# 4c_-_Latching_BSPD.net
KiCad netlist of a schematic drawn in Altium Designer
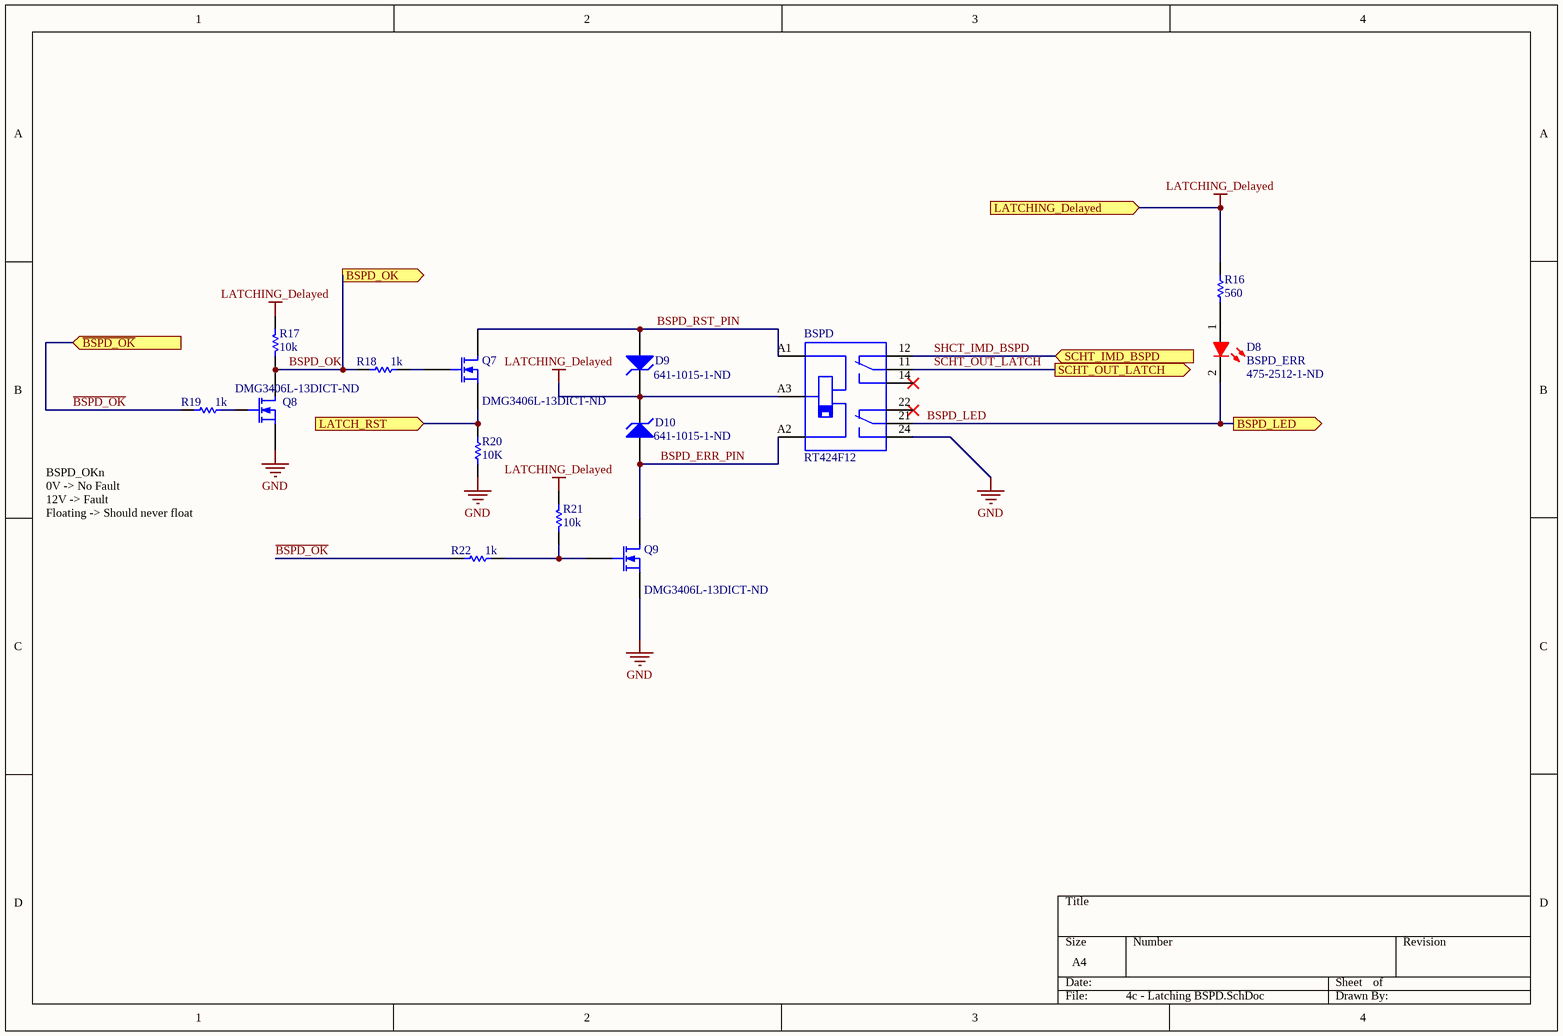
[diagram p0: 4c - Latching BSPD.SchDoc]

(export (version "E")
  (design (tool "Eeschema 10.0.6"))
  (components
    (comp (ref "BSPD")
      (value "RT424F12")
      (footprint "TE_5-1393243-4")
      (description "General Purpose Relay DPDT (2 Form C) 12VDC Coil Through Hole")
      (fields (field (name "MF") "TE Connectivity"))
      (libsource (lib "RT424F12") (part "RT424F12"))
    )
    (comp (ref "D8")
      (value "BSPD_ERR")
      (footprint "TOSH-0603LED_RED_V")
      (description "LED, Red 0603 (1608) 63mCd")
      (fields
        (field (name "MANUFACTURER") "Toshiba")
        (field (name "PARTNUMBER") "TLSU1008A(T04)")
        (field (name "SUPPLIER PART NUMBER 1") "475-2512-1-ND")
      )
      (libsource (lib "Altium Content Vault") (part "CMP-0444-00001-1"))
    )
    (comp (ref "D9")
      (value "D Zener")
      (footprint "DO214AC")
      (description "Zener Diode")
      (fields
        (field (name "SUPPLIER PART NUMBER 1") "641-1015-1-ND")
        (field (name "PUBLISHER") "Altium Limited")
      )
      (libsource (lib "Miscellaneous Devices") (part "D Zener"))
    )
    (comp (ref "D10")
      (value "D Zener")
      (footprint "DO214AC")
      (description "Zener Diode")
      (fields
        (field (name "SUPPLIER PART NUMBER 1") "641-1015-1-ND")
        (field (name "PUBLISHER") "Altium Limited")
      )
      (libsource (lib "Miscellaneous Devices") (part "D Zener"))
    )
    (comp (ref "Q7")
      (value "~")
      (footprint "SOT-23_N")
      (description "N-Channel MOSFET")
      (fields
        (field (name "MANUFACTURER") "Infineon Technologies")
        (field (name "SUPPLIER PART NUMBER 1") "DMG3406L-13DICT-ND")
        (field (name "PUBLISHER") "Altium Limited")
      )
      (libsource (lib "Miscellaneous Devices") (part "MOSFET-N"))
    )
    (comp (ref "Q8")
      (value "~")
      (footprint "SOT-23_N")
      (description "N-Channel MOSFET")
      (fields
        (field (name "MANUFACTURER") "Infineon Technologies")
        (field (name "SUPPLIER PART NUMBER 1") "DMG3406L-13DICT-ND")
        (field (name "PUBLISHER") "Altium Limited")
      )
      (libsource (lib "Miscellaneous Devices") (part "MOSFET-N"))
    )
    (comp (ref "Q9")
      (value "~")
      (footprint "SOT-23_N")
      (description "N-Channel MOSFET")
      (fields
        (field (name "MANUFACTURER") "Infineon Technologies")
        (field (name "SUPPLIER PART NUMBER 1") "DMG3406L-13DICT-ND")
        (field (name "PUBLISHER") "Altium Limited")
      )
      (libsource (lib "Miscellaneous Devices") (part "MOSFET-N"))
    )
    (comp (ref "R16")
      (value "560")
      (footprint "RESC0603(1608)_L")
      (description "0603 (1608 Metric) Chip Resistor")
      (libsource (lib "Altium Content Vault") (part "RES_3"))
    )
    (comp (ref "R17")
      (value "RHM1.0KDCT-ND")
      (footprint "1608[0603]")
      (description "RES SMD 1.0K OHM 5% 1/4W 0603")
      (fields
        (field (name "MANUFACTURER") "Rohm Semiconductor")
        (field (name "MANUFACTURER PART NUMBER") "ESR03EZPJ102")
        (field (name "RESISTANCE (OHMS)") "10k")
      )
      (libsource (lib "Miscellaneous Devices") (part "Res1"))
    )
    (comp (ref "R18")
      (value "1k")
      (footprint "1608[0603]")
      (description "RES SMD 100 OHM 5% 1/4W 0603")
      (fields
        (field (name "MANUFACTURER") "Rohm Semiconductor")
        (field (name "MANUFACTURER PART NUMBER") "ESR03EZPJ101")
        (field (name "PUBLISHER") "Altium Limited")
      )
      (libsource (lib "Miscellaneous Devices") (part "Res1"))
    )
    (comp (ref "R19")
      (value "1k")
      (footprint "1608[0603]")
      (description "RES SMD 100 OHM 5% 1/4W 0603")
      (fields
        (field (name "MANUFACTURER") "Rohm Semiconductor")
        (field (name "MANUFACTURER PART NUMBER") "ESR03EZPJ101")
        (field (name "PUBLISHER") "Altium Limited")
      )
      (libsource (lib "Miscellaneous Devices") (part "Res1"))
    )
    (comp (ref "R20")
      (value "10K")
      (footprint "1608[0603]")
      (description "RES SMD 10K OHM 5% 1/4W 0603")
      (fields
        (field (name "MANUFACTURER") "Rohm Semiconductor")
        (field (name "MANUFACTURER PART NUMBER") "ESR03EZPJ103")
        (field (name "PUBLISHER") "Altium Limited")
      )
      (libsource (lib "Miscellaneous Devices") (part "Res1"))
    )
    (comp (ref "R21")
      (value "RHM1.0KDCT-ND")
      (footprint "1608[0603]")
      (description "RES SMD 1.0K OHM 5% 1/4W 0603")
      (fields
        (field (name "MANUFACTURER") "Rohm Semiconductor")
        (field (name "MANUFACTURER PART NUMBER") "ESR03EZPJ102")
        (field (name "RESISTANCE (OHMS)") "10k")
      )
      (libsource (lib "Miscellaneous Devices") (part "Res1"))
    )
    (comp (ref "R22")
      (value "1k")
      (footprint "1608[0603]")
      (description "RES SMD 100 OHM 5% 1/4W 0603")
      (fields
        (field (name "MANUFACTURER") "Rohm Semiconductor")
        (field (name "MANUFACTURER PART NUMBER") "ESR03EZPJ101")
        (field (name "PUBLISHER") "Altium Limited")
      )
      (libsource (lib "Miscellaneous Devices") (part "Res1"))
    )
  )
  (nets
    (net (code "1") (name "/BSPD_ERR_PIN") (class "Default")
      (node (ref "BSPD") (pin "A2") (pinfunction "A2_A2") (pintype "passive"))
      (node (ref "D10") (pin "1") (pinfunction "A_1") (pintype "passive"))
      (node (ref "Q9") (pin "3") (pinfunction "D_3") (pintype "passive"))
    )
    (net (code "2") (name "/BSPD_LED") (class "Default")
      (node (ref "BSPD") (pin "21") (pinfunction "21_21") (pintype "passive"))
      (node (ref "D8") (pin "2") (pinfunction "K_2") (pintype "passive"))
    )
    (net (code "3") (name "/BSPD_OK") (class "Default")
      (node (ref "Q8") (pin "3") (pinfunction "D_3") (pintype "passive"))
      (node (ref "R17") (pin "2") (pinfunction "2_2") (pintype "passive"))
      (node (ref "R18") (pin "1") (pinfunction "1_1") (pintype "passive"))
    )
    (net (code "4") (name "/BSPD_RST_PIN") (class "Default")
      (node (ref "BSPD") (pin "A1") (pinfunction "A1_A1") (pintype "passive"))
      (node (ref "D9") (pin "1") (pinfunction "A_1") (pintype "passive"))
      (node (ref "Q7") (pin "3") (pinfunction "D_3") (pintype "passive"))
    )
    (net (code "5") (name "/LATCH_RST") (class "Default")
      (node (ref "Q7") (pin "2") (pinfunction "S_2") (pintype "passive"))
      (node (ref "R20") (pin "2") (pinfunction "2_2") (pintype "passive"))
    )
    (net (code "6") (name "/SCHT_OUT_LATCH") (class "Default")
      (node (ref "BSPD") (pin "11") (pinfunction "11_11") (pintype "passive"))
    )
    (net (code "7") (name "/SHCT_IMD_BSPD") (class "Default")
      (node (ref "BSPD") (pin "12") (pinfunction "12_12") (pintype "passive"))
    )
    (net (code "8") (name "/~{BSPD_OK}") (class "Default")
      (node (ref "R19") (pin "1") (pinfunction "1_1") (pintype "passive"))
      (node (ref "R22") (pin "1") (pinfunction "1_1") (pintype "passive"))
    )
    (net (code "9") (name "GND") (class "Default")
      (node (ref "BSPD") (pin "24") (pinfunction "24_24") (pintype "passive"))
      (node (ref "Q8") (pin "2") (pinfunction "S_2") (pintype "passive"))
      (node (ref "Q9") (pin "2") (pinfunction "S_2") (pintype "passive"))
      (node (ref "R20") (pin "1") (pinfunction "1_1") (pintype "passive"))
    )
    (net (code "10") (name "LATCHING_Delayed") (class "Default")
      (node (ref "BSPD") (pin "A3") (pinfunction "A3_A3") (pintype "passive"))
      (node (ref "D10") (pin "2") (pinfunction "K_2") (pintype "passive"))
      (node (ref "D9") (pin "2") (pinfunction "K_2") (pintype "passive"))
      (node (ref "R16") (pin "2") (pinfunction "2_2") (pintype "passive"))
      (node (ref "R17") (pin "1") (pinfunction "1_1") (pintype "passive"))
      (node (ref "R21") (pin "1") (pinfunction "1_1") (pintype "passive"))
    )
    (net (code "11") (name "Net-(D8-A)") (class "Default")
      (node (ref "D8") (pin "1") (pinfunction "A_1") (pintype "passive"))
      (node (ref "R16") (pin "1") (pinfunction "1_1") (pintype "passive"))
    )
    (net (code "12") (name "Net-(Q7-G)") (class "Default")
      (node (ref "Q7") (pin "1") (pinfunction "G_1") (pintype "passive"))
      (node (ref "R18") (pin "2") (pinfunction "2_2") (pintype "passive"))
    )
    (net (code "13") (name "Net-(Q8-G)") (class "Default")
      (node (ref "Q8") (pin "1") (pinfunction "G_1") (pintype "passive"))
      (node (ref "R19") (pin "2") (pinfunction "2_2") (pintype "passive"))
    )
    (net (code "14") (name "Net-(Q9-G)") (class "Default")
      (node (ref "Q9") (pin "1") (pinfunction "G_1") (pintype "passive"))
      (node (ref "R21") (pin "2") (pinfunction "2_2") (pintype "passive"))
      (node (ref "R22") (pin "2") (pinfunction "2_2") (pintype "passive"))
    )
    (net (code "15") (name "unconnected-(BSPD-Pad14)") (class "Default")
      (node (ref "BSPD") (pin "14") (pinfunction "14_14") (pintype "passive+no_connect"))
    )
    (net (code "16") (name "unconnected-(BSPD-Pad22)") (class "Default")
      (node (ref "BSPD") (pin "22") (pinfunction "22_22") (pintype "passive+no_connect"))
    )
  )
)
